# Supply_Protection.net
KiCad netlist of a schematic drawn in Altium Designer
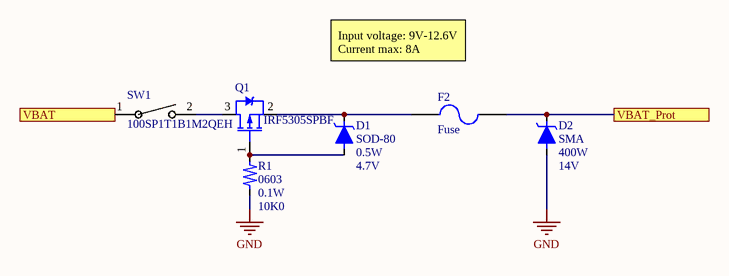
[diagram p0: Supply_Protection.SchDoc]

(export (version "E")
  (design (tool "Eeschema 10.0.6"))
  (components
    (comp (ref "D1")
      (value "SOD-80")
      (footprint "SOD-80")
      (fields
        (field (name "PART NUMBER") "TZMC4V7GS08")
        (field (name "RATING") "0.5W")
        (field (name "ALTIUM_VALUE") "4.7V")
      )
      (libsource (lib "Components") (part "Diode_Zener"))
    )
    (comp (ref "D2")
      (value "SMA")
      (footprint "SMA")
      (fields
        (field (name "PART NUMBER") "SMAJ12A")
        (field (name "RATING") "400W")
        (field (name "ALTIUM_VALUE") "14V")
      )
      (libsource (lib "Components") (part "Diode_Transient_Sup"))
    )
    (comp (ref "F2")
      (value "Fuse")
      (footprint "F_2410")
      (fields (field (name "PART NUMBER") "0451003.MRL"))
      (libsource (lib "Components") (part "Fuse"))
    )
    (comp (ref "Q1")
      (value "IRF5305SPBF")
      (footprint "D2PAK-2")
      (description "P-Channel Power MOSFET")
      (libsource (lib "Components") (part "Transistor_P-FET"))
    )
    (comp (ref "R1")
      (value "0603")
      (footprint "R_0603")
      (fields
        (field (name "TOLERANCE") "1%")
        (field (name "PART NUMBER") "CR-03FL7---10K")
        (field (name "RATING") "0.1W")
        (field (name "ALTIUM_VALUE") "10K0")
        (field (name "NI PART NUMBER") "713771-01")
      )
      (libsource (lib "Components") (part "Resistor_Chip"))
    )
    (comp (ref "SW1")
      (value "100SP1T1B1M2QEH")
      (footprint "100SP1T1B1M2QEH:SW_100SP1T_12P7X6P86_EWI")
      (description "No Description Available")
      (fields (field (name "COPYRIGHT") "Copyright (C) 2023 Ultra Librarian. All rights reserved."))
      (libsource (lib "100SP1T1B1M2QEH") (part "100SP1T1B1M2QEH"))
    )
  )
  (nets
    (net (code "1") (name "/VBAT") (class "Default")
      (node (ref "SW1") (pin "1") (pinfunction "1_1") (pintype "passive"))
    )
    (net (code "2") (name "/VBAT_Prot") (class "Default")
      (node (ref "D2") (pin "1") (pinfunction "DC_1") (pintype "passive"))
      (node (ref "F2") (pin "2") (pinfunction "2_2") (pintype "passive"))
    )
    (net (code "3") (name "GND") (class "Default")
      (node (ref "D2") (pin "2") (pinfunction "DA_2") (pintype "passive"))
      (node (ref "R1") (pin "1") (pinfunction "R1_1") (pintype "passive"))
    )
    (net (code "4") (name "Net-(D1-DA)") (class "Default")
      (node (ref "D1") (pin "2") (pinfunction "DA_2") (pintype "passive"))
      (node (ref "Q1") (pin "1") (pinfunction "G_1") (pintype "passive"))
      (node (ref "R1") (pin "2") (pinfunction "R2_2") (pintype "passive"))
    )
    (net (code "5") (name "Net-(D1-DC)") (class "Default")
      (node (ref "D1") (pin "1") (pinfunction "DC_1") (pintype "passive"))
      (node (ref "F2") (pin "1") (pinfunction "1_1") (pintype "passive"))
      (node (ref "Q1") (pin "2") (pinfunction "S_2") (pintype "passive"))
    )
    (net (code "6") (name "Net-(Q1-D)") (class "Default")
      (node (ref "Q1") (pin "3") (pinfunction "D_3") (pintype "passive"))
      (node (ref "SW1") (pin "2") (pinfunction "2_2") (pintype "passive"))
    )
  )
)
